# Register_16B.net
KiCad netlist of a schematic drawn in Altium Designer
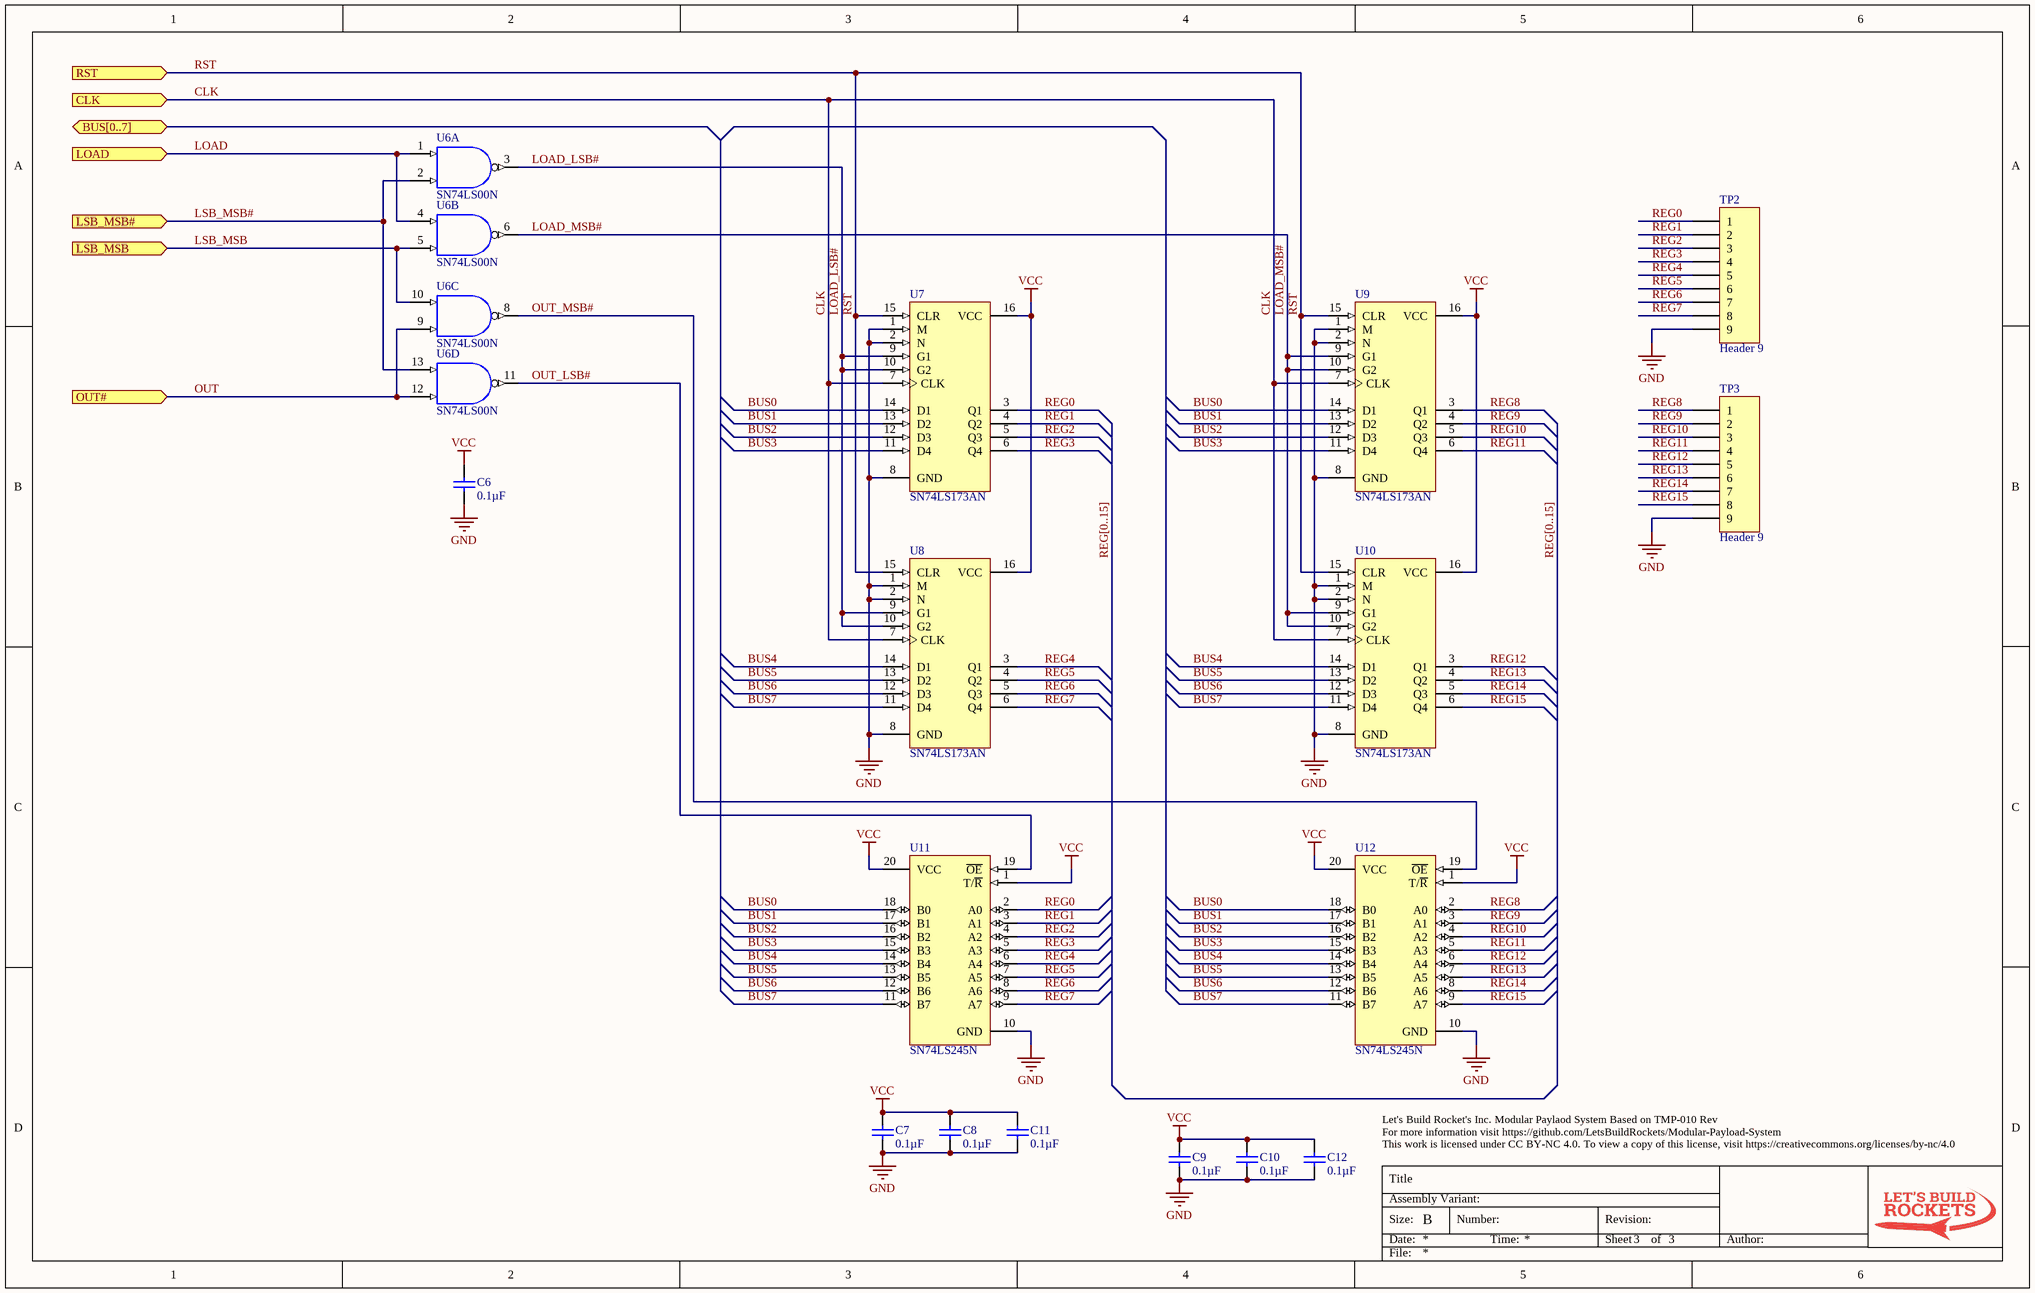
[diagram p0: Register_16B.SchDoc]

(export (version "E")
  (design (tool "Eeschema 10.0.6"))
  (components
    (comp (ref "C6")
      (value "K104K15X7RF5TL2")
      (footprint "VISH-K104K15X7RF5TL2")
      (description "Ceramic Capacitor, 100 nF, +/- 10%, 50 V, -55 to 125 degC, 2-Pin THD, RoHS, Tape and Reel")
      (fields
        (field (name "MANUFACTURER") "Vishay")
        (field (name "TOLERANCE") "±10%")
        (field (name "CAPACITANCE") "0.1µF")
      )
      (libsource (lib "Altium Content Vault") (part "CAP-NP-2"))
    )
    (comp (ref "C7")
      (value "K104K15X7RF5TL2")
      (footprint "VISH-K104K15X7RF5TL2")
      (description "Ceramic Capacitor, 100 nF, +/- 10%, 50 V, -55 to 125 degC, 2-Pin THD, RoHS, Tape and Reel")
      (fields
        (field (name "MANUFACTURER") "Vishay")
        (field (name "TOLERANCE") "±10%")
        (field (name "CAPACITANCE") "0.1µF")
      )
      (libsource (lib "Altium Content Vault") (part "CAP-NP-2"))
    )
    (comp (ref "C8")
      (value "K104K15X7RF5TL2")
      (footprint "VISH-K104K15X7RF5TL2")
      (description "Ceramic Capacitor, 100 nF, +/- 10%, 50 V, -55 to 125 degC, 2-Pin THD, RoHS, Tape and Reel")
      (fields
        (field (name "MANUFACTURER") "Vishay")
        (field (name "TOLERANCE") "±10%")
        (field (name "CAPACITANCE") "0.1µF")
      )
      (libsource (lib "Altium Content Vault") (part "CAP-NP-2"))
    )
    (comp (ref "C9")
      (value "K104K15X7RF5TL2")
      (footprint "VISH-K104K15X7RF5TL2")
      (description "Ceramic Capacitor, 100 nF, +/- 10%, 50 V, -55 to 125 degC, 2-Pin THD, RoHS, Tape and Reel")
      (fields
        (field (name "MANUFACTURER") "Vishay")
        (field (name "TOLERANCE") "±10%")
        (field (name "CAPACITANCE") "0.1µF")
      )
      (libsource (lib "Altium Content Vault") (part "CAP-NP-2"))
    )
    (comp (ref "C10")
      (value "K104K15X7RF5TL2")
      (footprint "VISH-K104K15X7RF5TL2")
      (description "Ceramic Capacitor, 100 nF, +/- 10%, 50 V, -55 to 125 degC, 2-Pin THD, RoHS, Tape and Reel")
      (fields
        (field (name "MANUFACTURER") "Vishay")
        (field (name "TOLERANCE") "±10%")
        (field (name "CAPACITANCE") "0.1µF")
      )
      (libsource (lib "Altium Content Vault") (part "CAP-NP-2"))
    )
    (comp (ref "C11")
      (value "K104K15X7RF5TL2")
      (footprint "VISH-K104K15X7RF5TL2")
      (description "Ceramic Capacitor, 100 nF, +/- 10%, 50 V, -55 to 125 degC, 2-Pin THD, RoHS, Tape and Reel")
      (fields
        (field (name "MANUFACTURER") "Vishay")
        (field (name "TOLERANCE") "±10%")
        (field (name "CAPACITANCE") "0.1µF")
      )
      (libsource (lib "Altium Content Vault") (part "CAP-NP-2"))
    )
    (comp (ref "C12")
      (value "K104K15X7RF5TL2")
      (footprint "VISH-K104K15X7RF5TL2")
      (description "Ceramic Capacitor, 100 nF, +/- 10%, 50 V, -55 to 125 degC, 2-Pin THD, RoHS, Tape and Reel")
      (fields
        (field (name "MANUFACTURER") "Vishay")
        (field (name "TOLERANCE") "±10%")
        (field (name "CAPACITANCE") "0.1µF")
      )
      (libsource (lib "Altium Content Vault") (part "CAP-NP-2"))
    )
    (comp (ref "TP2")
      (value "Header 9")
      (footprint "HDR1X9")
      (description "Header, 9-Pin")
      (fields (field (name "PUBLISHER") "Altium Limited"))
      (libsource (lib "Miscellaneous Connectors") (part "Header 9"))
    )
    (comp (ref "TP3")
      (value "Header 9")
      (footprint "HDR1X9")
      (description "Header, 9-Pin")
      (fields (field (name "PUBLISHER") "Altium Limited"))
      (libsource (lib "Miscellaneous Connectors") (part "Header 9"))
    )
    (comp (ref "U6")
      (value "SN74LS00N")
      (footprint "N014")
      (description "Quadruple 2-Input Positive-NAND Gate")
      (fields (field (name "PUBLISHER") "Altium Limited"))
      (libsource (lib "TI Logic Gate 2") (part "SN74LS00N"))
    )
    (comp (ref "U7")
      (value "SN74LS173AN")
      (footprint "N016D")
      (description "4-Bit D-Type Register with 3-State Outputs")
      (fields (field (name "PUBLISHER") "Altium Limited"))
      (libsource (lib "TI Logic Flip-Flop") (part "SN74LS173AN"))
    )
    (comp (ref "U8")
      (value "SN74LS173AN")
      (footprint "N016D")
      (description "4-Bit D-Type Register with 3-State Outputs")
      (fields (field (name "PUBLISHER") "Altium Limited"))
      (libsource (lib "TI Logic Flip-Flop") (part "SN74LS173AN"))
    )
    (comp (ref "U9")
      (value "SN74LS173AN")
      (footprint "N016D")
      (description "4-Bit D-Type Register with 3-State Outputs")
      (fields (field (name "PUBLISHER") "Altium Limited"))
      (libsource (lib "TI Logic Flip-Flop") (part "SN74LS173AN"))
    )
    (comp (ref "U10")
      (value "SN74LS173AN")
      (footprint "N016D")
      (description "4-Bit D-Type Register with 3-State Outputs")
      (fields (field (name "PUBLISHER") "Altium Limited"))
      (libsource (lib "TI Logic Flip-Flop") (part "SN74LS173AN"))
    )
    (comp (ref "U11")
      (value "SN74LS245N")
      (footprint "N020")
      (description "Octal Bus Transceiver with 3-State Outputs")
      (fields (field (name "PUBLISHER") "Altium Limited"))
      (libsource (lib "TI Interface 8-Bit Line Transceiver") (part "SN74LS245N"))
    )
    (comp (ref "U12")
      (value "SN74LS245N")
      (footprint "N020")
      (description "Octal Bus Transceiver with 3-State Outputs")
      (fields (field (name "PUBLISHER") "Altium Limited"))
      (libsource (lib "TI Interface 8-Bit Line Transceiver") (part "SN74LS245N"))
    )
  )
  (nets
    (net (code "1") (name "/BUS0") (class "Default")
      (node (ref "U11") (pin "18") (pinfunction "B0_18") (pintype "bidirectional"))
      (node (ref "U12") (pin "18") (pinfunction "B0_18") (pintype "bidirectional"))
      (node (ref "U7") (pin "14") (pinfunction "D1_14") (pintype "input"))
      (node (ref "U9") (pin "14") (pinfunction "D1_14") (pintype "input"))
    )
    (net (code "2") (name "/BUS1") (class "Default")
      (node (ref "U11") (pin "17") (pinfunction "B1_17") (pintype "bidirectional"))
      (node (ref "U12") (pin "17") (pinfunction "B1_17") (pintype "bidirectional"))
      (node (ref "U7") (pin "13") (pinfunction "D2_13") (pintype "input"))
      (node (ref "U9") (pin "13") (pinfunction "D2_13") (pintype "input"))
    )
    (net (code "3") (name "/BUS2") (class "Default")
      (node (ref "U11") (pin "16") (pinfunction "B2_16") (pintype "bidirectional"))
      (node (ref "U12") (pin "16") (pinfunction "B2_16") (pintype "bidirectional"))
      (node (ref "U7") (pin "12") (pinfunction "D3_12") (pintype "input"))
      (node (ref "U9") (pin "12") (pinfunction "D3_12") (pintype "input"))
    )
    (net (code "4") (name "/BUS3") (class "Default")
      (node (ref "U11") (pin "15") (pinfunction "B3_15") (pintype "bidirectional"))
      (node (ref "U12") (pin "15") (pinfunction "B3_15") (pintype "bidirectional"))
      (node (ref "U7") (pin "11") (pinfunction "D4_11") (pintype "input"))
      (node (ref "U9") (pin "11") (pinfunction "D4_11") (pintype "input"))
    )
    (net (code "5") (name "/BUS4") (class "Default")
      (node (ref "U10") (pin "14") (pinfunction "D1_14") (pintype "input"))
      (node (ref "U11") (pin "14") (pinfunction "B4_14") (pintype "bidirectional"))
      (node (ref "U12") (pin "14") (pinfunction "B4_14") (pintype "bidirectional"))
      (node (ref "U8") (pin "14") (pinfunction "D1_14") (pintype "input"))
    )
    (net (code "6") (name "/BUS5") (class "Default")
      (node (ref "U10") (pin "13") (pinfunction "D2_13") (pintype "input"))
      (node (ref "U11") (pin "13") (pinfunction "B5_13") (pintype "bidirectional"))
      (node (ref "U12") (pin "13") (pinfunction "B5_13") (pintype "bidirectional"))
      (node (ref "U8") (pin "13") (pinfunction "D2_13") (pintype "input"))
    )
    (net (code "7") (name "/BUS6") (class "Default")
      (node (ref "U10") (pin "12") (pinfunction "D3_12") (pintype "input"))
      (node (ref "U11") (pin "12") (pinfunction "B6_12") (pintype "bidirectional"))
      (node (ref "U12") (pin "12") (pinfunction "B6_12") (pintype "bidirectional"))
      (node (ref "U8") (pin "12") (pinfunction "D3_12") (pintype "input"))
    )
    (net (code "8") (name "/BUS7") (class "Default")
      (node (ref "U10") (pin "11") (pinfunction "D4_11") (pintype "input"))
      (node (ref "U11") (pin "11") (pinfunction "B7_11") (pintype "bidirectional"))
      (node (ref "U12") (pin "11") (pinfunction "B7_11") (pintype "bidirectional"))
      (node (ref "U8") (pin "11") (pinfunction "D4_11") (pintype "input"))
    )
    (net (code "10") (name "/CLK") (class "Default")
      (node (ref "U10") (pin "7") (pinfunction "CLK_7") (pintype "input"))
      (node (ref "U7") (pin "7") (pinfunction "CLK_7") (pintype "input"))
      (node (ref "U8") (pin "7") (pinfunction "CLK_7") (pintype "input"))
      (node (ref "U9") (pin "7") (pinfunction "CLK_7") (pintype "input"))
    )
    (net (code "11") (name "/LOAD") (class "Default")
      (node (ref "U6") (pin "1") (pinfunction "A_1") (pintype "input"))
      (node (ref "U6") (pin "4") (pinfunction "A_4") (pintype "input"))
    )
    (net (code "12") (name "/LOAD_LSB#") (class "Default")
      (node (ref "U6") (pin "3") (pinfunction "Y_3") (pintype "output"))
      (node (ref "U7") (pin "10") (pinfunction "G2_10") (pintype "input"))
      (node (ref "U7") (pin "9") (pinfunction "G1_9") (pintype "input"))
      (node (ref "U8") (pin "10") (pinfunction "G2_10") (pintype "input"))
      (node (ref "U8") (pin "9") (pinfunction "G1_9") (pintype "input"))
    )
    (net (code "13") (name "/LOAD_MSB#") (class "Default")
      (node (ref "U10") (pin "10") (pinfunction "G2_10") (pintype "input"))
      (node (ref "U10") (pin "9") (pinfunction "G1_9") (pintype "input"))
      (node (ref "U6") (pin "6") (pinfunction "Y_6") (pintype "output"))
      (node (ref "U9") (pin "10") (pinfunction "G2_10") (pintype "input"))
      (node (ref "U9") (pin "9") (pinfunction "G1_9") (pintype "input"))
    )
    (net (code "14") (name "/LSB_MSB") (class "Default")
      (node (ref "U6") (pin "10") (pinfunction "B_10") (pintype "input"))
      (node (ref "U6") (pin "5") (pinfunction "B_5") (pintype "input"))
    )
    (net (code "15") (name "/LSB_MSB#") (class "Default")
      (node (ref "U6") (pin "13") (pinfunction "B_13") (pintype "input"))
      (node (ref "U6") (pin "2") (pinfunction "B_2") (pintype "input"))
    )
    (net (code "16") (name "/OUT") (class "Default")
      (node (ref "U6") (pin "12") (pinfunction "A_12") (pintype "input"))
      (node (ref "U6") (pin "9") (pinfunction "A_9") (pintype "input"))
    )
    (net (code "17") (name "/OUT_LSB#") (class "Default")
      (node (ref "U11") (pin "19") (pinfunction "~{OE}_19") (pintype "input"))
      (node (ref "U6") (pin "11") (pinfunction "Y_11") (pintype "output"))
    )
    (net (code "18") (name "/OUT_MSB#") (class "Default")
      (node (ref "U12") (pin "19") (pinfunction "~{OE}_19") (pintype "input"))
      (node (ref "U6") (pin "8") (pinfunction "Y_8") (pintype "output"))
    )
    (net (code "19") (name "/REG0") (class "Default")
      (node (ref "TP2") (pin "1") (pinfunction "1_1") (pintype "passive"))
      (node (ref "U11") (pin "2") (pinfunction "A0_2") (pintype "bidirectional"))
      (node (ref "U7") (pin "3") (pinfunction "Q1_3") (pintype "tri_state"))
    )
    (net (code "20") (name "/REG1") (class "Default")
      (node (ref "TP2") (pin "2") (pinfunction "2_2") (pintype "passive"))
      (node (ref "U11") (pin "3") (pinfunction "A1_3") (pintype "bidirectional"))
      (node (ref "U7") (pin "4") (pinfunction "Q2_4") (pintype "tri_state"))
    )
    (net (code "21") (name "/REG2") (class "Default")
      (node (ref "TP2") (pin "3") (pinfunction "3_3") (pintype "passive"))
      (node (ref "U11") (pin "4") (pinfunction "A2_4") (pintype "bidirectional"))
      (node (ref "U7") (pin "5") (pinfunction "Q3_5") (pintype "tri_state"))
    )
    (net (code "22") (name "/REG3") (class "Default")
      (node (ref "TP2") (pin "4") (pinfunction "4_4") (pintype "passive"))
      (node (ref "U11") (pin "5") (pinfunction "A3_5") (pintype "bidirectional"))
      (node (ref "U7") (pin "6") (pinfunction "Q4_6") (pintype "tri_state"))
    )
    (net (code "23") (name "/REG4") (class "Default")
      (node (ref "TP2") (pin "5") (pinfunction "5_5") (pintype "passive"))
      (node (ref "U11") (pin "6") (pinfunction "A4_6") (pintype "bidirectional"))
      (node (ref "U8") (pin "3") (pinfunction "Q1_3") (pintype "tri_state"))
    )
    (net (code "24") (name "/REG5") (class "Default")
      (node (ref "TP2") (pin "6") (pinfunction "6_6") (pintype "passive"))
      (node (ref "U11") (pin "7") (pinfunction "A5_7") (pintype "bidirectional"))
      (node (ref "U8") (pin "4") (pinfunction "Q2_4") (pintype "tri_state"))
    )
    (net (code "25") (name "/REG6") (class "Default")
      (node (ref "TP2") (pin "7") (pinfunction "7_7") (pintype "passive"))
      (node (ref "U11") (pin "8") (pinfunction "A6_8") (pintype "bidirectional"))
      (node (ref "U8") (pin "5") (pinfunction "Q3_5") (pintype "tri_state"))
    )
    (net (code "26") (name "/REG7") (class "Default")
      (node (ref "TP2") (pin "8") (pinfunction "8_8") (pintype "passive"))
      (node (ref "U11") (pin "9") (pinfunction "A7_9") (pintype "bidirectional"))
      (node (ref "U8") (pin "6") (pinfunction "Q4_6") (pintype "tri_state"))
    )
    (net (code "27") (name "/REG8") (class "Default")
      (node (ref "TP3") (pin "1") (pinfunction "1_1") (pintype "passive"))
      (node (ref "U12") (pin "2") (pinfunction "A0_2") (pintype "bidirectional"))
      (node (ref "U9") (pin "3") (pinfunction "Q1_3") (pintype "tri_state"))
    )
    (net (code "28") (name "/REG9") (class "Default")
      (node (ref "TP3") (pin "2") (pinfunction "2_2") (pintype "passive"))
      (node (ref "U12") (pin "3") (pinfunction "A1_3") (pintype "bidirectional"))
      (node (ref "U9") (pin "4") (pinfunction "Q2_4") (pintype "tri_state"))
    )
    (net (code "29") (name "/REG10") (class "Default")
      (node (ref "TP3") (pin "3") (pinfunction "3_3") (pintype "passive"))
      (node (ref "U12") (pin "4") (pinfunction "A2_4") (pintype "bidirectional"))
      (node (ref "U9") (pin "5") (pinfunction "Q3_5") (pintype "tri_state"))
    )
    (net (code "30") (name "/REG11") (class "Default")
      (node (ref "TP3") (pin "4") (pinfunction "4_4") (pintype "passive"))
      (node (ref "U12") (pin "5") (pinfunction "A3_5") (pintype "bidirectional"))
      (node (ref "U9") (pin "6") (pinfunction "Q4_6") (pintype "tri_state"))
    )
    (net (code "31") (name "/REG12") (class "Default")
      (node (ref "TP3") (pin "5") (pinfunction "5_5") (pintype "passive"))
      (node (ref "U10") (pin "3") (pinfunction "Q1_3") (pintype "tri_state"))
      (node (ref "U12") (pin "6") (pinfunction "A4_6") (pintype "bidirectional"))
    )
    (net (code "32") (name "/REG13") (class "Default")
      (node (ref "TP3") (pin "6") (pinfunction "6_6") (pintype "passive"))
      (node (ref "U10") (pin "4") (pinfunction "Q2_4") (pintype "tri_state"))
      (node (ref "U12") (pin "7") (pinfunction "A5_7") (pintype "bidirectional"))
    )
    (net (code "33") (name "/REG14") (class "Default")
      (node (ref "TP3") (pin "7") (pinfunction "7_7") (pintype "passive"))
      (node (ref "U10") (pin "5") (pinfunction "Q3_5") (pintype "tri_state"))
      (node (ref "U12") (pin "8") (pinfunction "A6_8") (pintype "bidirectional"))
    )
    (net (code "34") (name "/REG15") (class "Default")
      (node (ref "TP3") (pin "8") (pinfunction "8_8") (pintype "passive"))
      (node (ref "U10") (pin "6") (pinfunction "Q4_6") (pintype "tri_state"))
      (node (ref "U12") (pin "9") (pinfunction "A7_9") (pintype "bidirectional"))
    )
    (net (code "36") (name "/RST") (class "Default")
      (node (ref "U10") (pin "15") (pinfunction "CLR_15") (pintype "input"))
      (node (ref "U7") (pin "15") (pinfunction "CLR_15") (pintype "input"))
      (node (ref "U8") (pin "15") (pinfunction "CLR_15") (pintype "input"))
      (node (ref "U9") (pin "15") (pinfunction "CLR_15") (pintype "input"))
    )
    (net (code "37") (name "GND") (class "Default")
      (node (ref "C10") (pin "2") (pinfunction "2_2") (pintype "passive"))
      (node (ref "C11") (pin "2") (pinfunction "2_2") (pintype "passive"))
      (node (ref "C12") (pin "2") (pinfunction "2_2") (pintype "passive"))
      (node (ref "C6") (pin "2") (pinfunction "2_2") (pintype "passive"))
      (node (ref "C7") (pin "2") (pinfunction "2_2") (pintype "passive"))
      (node (ref "C8") (pin "2") (pinfunction "2_2") (pintype "passive"))
      (node (ref "C9") (pin "2") (pinfunction "2_2") (pintype "passive"))
      (node (ref "TP2") (pin "9") (pinfunction "9_9") (pintype "passive"))
      (node (ref "TP3") (pin "9") (pinfunction "9_9") (pintype "passive"))
      (node (ref "U10") (pin "1") (pinfunction "M_1") (pintype "input"))
      (node (ref "U10") (pin "2") (pinfunction "N_2") (pintype "input"))
      (node (ref "U10") (pin "8") (pinfunction "GND_8") (pintype "power_in"))
      (node (ref "U11") (pin "10") (pinfunction "GND_10") (pintype "power_in"))
      (node (ref "U12") (pin "10") (pinfunction "GND_10") (pintype "power_in"))
      (node (ref "U6") (pin "7") (pinfunction "GND_7") (pintype "power_in"))
      (node (ref "U7") (pin "1") (pinfunction "M_1") (pintype "input"))
      (node (ref "U7") (pin "2") (pinfunction "N_2") (pintype "input"))
      (node (ref "U7") (pin "8") (pinfunction "GND_8") (pintype "power_in"))
      (node (ref "U8") (pin "1") (pinfunction "M_1") (pintype "input"))
      (node (ref "U8") (pin "2") (pinfunction "N_2") (pintype "input"))
      (node (ref "U8") (pin "8") (pinfunction "GND_8") (pintype "power_in"))
      (node (ref "U9") (pin "1") (pinfunction "M_1") (pintype "input"))
      (node (ref "U9") (pin "2") (pinfunction "N_2") (pintype "input"))
      (node (ref "U9") (pin "8") (pinfunction "GND_8") (pintype "power_in"))
    )
    (net (code "38") (name "VCC") (class "Default")
      (node (ref "C10") (pin "1") (pinfunction "1_1") (pintype "passive"))
      (node (ref "C11") (pin "1") (pinfunction "1_1") (pintype "passive"))
      (node (ref "C12") (pin "1") (pinfunction "1_1") (pintype "passive"))
      (node (ref "C6") (pin "1") (pinfunction "1_1") (pintype "passive"))
      (node (ref "C7") (pin "1") (pinfunction "1_1") (pintype "passive"))
      (node (ref "C8") (pin "1") (pinfunction "1_1") (pintype "passive"))
      (node (ref "C9") (pin "1") (pinfunction "1_1") (pintype "passive"))
      (node (ref "U10") (pin "16") (pinfunction "VCC_16") (pintype "power_in"))
      (node (ref "U11") (pin "1") (pinfunction "T/~{R}_1") (pintype "input"))
      (node (ref "U11") (pin "20") (pinfunction "VCC_20") (pintype "power_in"))
      (node (ref "U12") (pin "1") (pinfunction "T/~{R}_1") (pintype "input"))
      (node (ref "U12") (pin "20") (pinfunction "VCC_20") (pintype "power_in"))
      (node (ref "U6") (pin "14") (pinfunction "VCC_14") (pintype "power_in"))
      (node (ref "U7") (pin "16") (pinfunction "VCC_16") (pintype "power_in"))
      (node (ref "U8") (pin "16") (pinfunction "VCC_16") (pintype "power_in"))
      (node (ref "U9") (pin "16") (pinfunction "VCC_16") (pintype "power_in"))
    )
  )
)
